# RGBW_Controller31.net
KiCad netlist of a schematic drawn in EAGLE
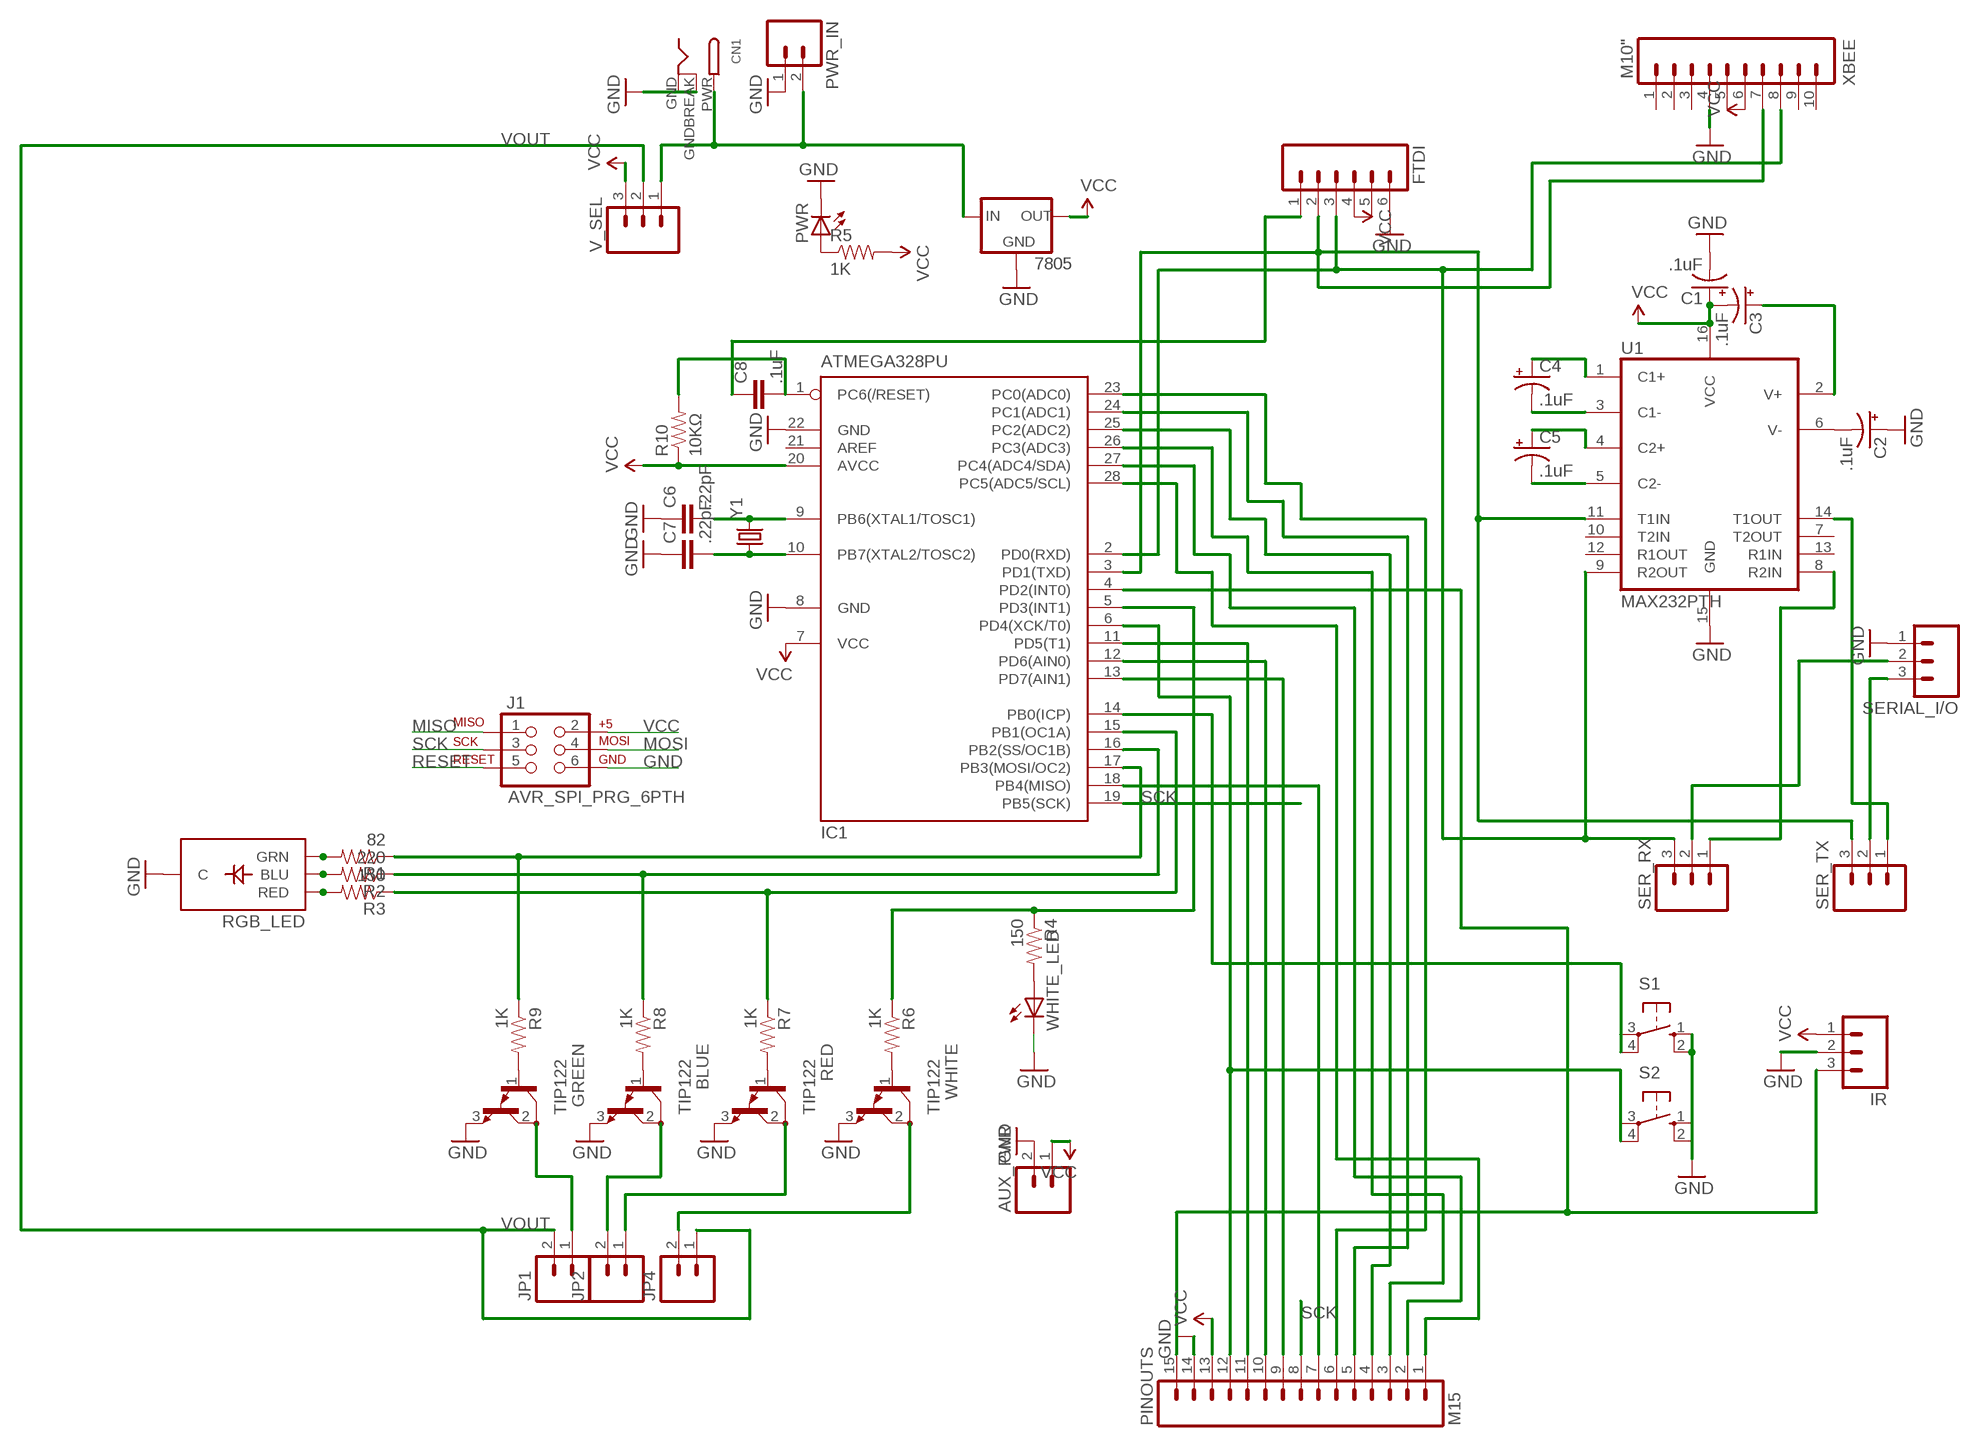
[diagram p0: schematic, sheet 1]

(export (version "E")
  (design (tool "Eeschema 10.0.6"))
  (components
    (comp (ref "7805")
      (value "V_REG_78XXSIDE")
      (footprint "eagle-import:78XXL")
      (libsource (lib "eagle-import") (part "V_REG_78XXSIDE"))
    )
    (comp (ref "AUX_PWR")
      (value "M02PTH")
      (footprint "eagle-import:1X02")
      (libsource (lib "eagle-import") (part "M02PTH"))
    )
    (comp (ref "BLUE")
      (value "TIP122")
      (footprint "eagle-import:TO220")
      (libsource (lib "eagle-import") (part "TIP122"))
    )
    (comp (ref "C1")
      (value ".1uF")
      (footprint "eagle-import:CPOL-RADIAL-100UF-25V")
      (libsource (lib "eagle-import") (part "CAP_POLPTH1"))
    )
    (comp (ref "C2")
      (value ".1uF")
      (footprint "eagle-import:CPOL-RADIAL-100UF-25V")
      (libsource (lib "eagle-import") (part "CAP_POLPTH1"))
    )
    (comp (ref "C3")
      (value ".1uF")
      (footprint "eagle-import:CPOL-RADIAL-100UF-25V")
      (libsource (lib "eagle-import") (part "CAP_POLPTH1"))
    )
    (comp (ref "C4")
      (value ".1uF")
      (footprint "eagle-import:CPOL-RADIAL-100UF-25V")
      (libsource (lib "eagle-import") (part "CAP_POLPTH1"))
    )
    (comp (ref "C5")
      (value ".1uF")
      (footprint "eagle-import:CPOL-RADIAL-100UF-25V")
      (libsource (lib "eagle-import") (part "CAP_POLPTH1"))
    )
    (comp (ref "C6")
      (value ".22pF")
      (footprint "eagle-import:CAP-PTH-SMALL")
      (libsource (lib "eagle-import") (part "CAPPTH"))
    )
    (comp (ref "C7")
      (value ".22pF")
      (footprint "eagle-import:CAP-PTH-SMALL")
      (libsource (lib "eagle-import") (part "CAPPTH"))
    )
    (comp (ref "C8")
      (value ".1uF")
      (footprint "eagle-import:CAP-PTH-SMALL-KIT")
      (libsource (lib "eagle-import") (part "CAPKIT"))
    )
    (comp (ref "CN1")
      (value "DCBARRELPTH")
      (footprint "eagle-import:DCJACK_2MM_PTH")
      (libsource (lib "eagle-import") (part "DCBARRELPTH"))
    )
    (comp (ref "FTDI")
      (value "M06SIP")
      (footprint "eagle-import:1X06")
      (libsource (lib "eagle-import") (part "M06SIP"))
    )
    (comp (ref "GREEN")
      (value "TIP122")
      (footprint "eagle-import:TO220")
      (libsource (lib "eagle-import") (part "TIP122"))
    )
    (comp (ref "IC1")
      (value "ATMEGA328PU")
      (footprint "eagle-import:DIL28-3")
      (libsource (lib "eagle-import") (part "MEGA8-P"))
    )
    (comp (ref "IR")
      (value "M03PTH")
      (footprint "eagle-import:1X03")
      (libsource (lib "eagle-import") (part "M03PTH"))
    )
    (comp (ref "J1")
      (value "AVR_SPI_PRG_6PTH")
      (footprint "eagle-import:2X3")
      (libsource (lib "eagle-import") (part "AVR_SPI_PRG_6PTH"))
    )
    (comp (ref "JP1")
      (value "M025MM")
      (footprint "eagle-import:SCREWTERMINAL-5MM-2")
      (libsource (lib "eagle-import") (part "M025MM"))
    )
    (comp (ref "JP2")
      (value "M025MM")
      (footprint "eagle-import:SCREWTERMINAL-5MM-2")
      (libsource (lib "eagle-import") (part "M025MM"))
    )
    (comp (ref "JP4")
      (value "M025MM")
      (footprint "eagle-import:SCREWTERMINAL-5MM-2")
      (libsource (lib "eagle-import") (part "M025MM"))
    )
    (comp (ref "PINOUTS")
      (value "M15")
      (footprint "eagle-import:1X15")
      (libsource (lib "eagle-import") (part "M15"))
    )
    (comp (ref "PWR")
      (value "LED5MM")
      (footprint "eagle-import:LED5MM")
      (libsource (lib "eagle-import") (part "LED5MM"))
    )
    (comp (ref "PWR_IN")
      (value "M025MM")
      (footprint "eagle-import:SCREWTERMINAL-5MM-2")
      (libsource (lib "eagle-import") (part "M025MM"))
    )
    (comp (ref "R1")
      (value "82")
      (footprint "eagle-import:AXIAL-0.4")
      (libsource (lib "eagle-import") (part "RESISTORPTH-1/4W"))
    )
    (comp (ref "R2")
      (value "220")
      (footprint "eagle-import:AXIAL-0.4")
      (libsource (lib "eagle-import") (part "RESISTORPTH-1/4W"))
    )
    (comp (ref "R3")
      (value "150")
      (footprint "eagle-import:AXIAL-0.4")
      (libsource (lib "eagle-import") (part "RESISTORPTH-1/4W"))
    )
    (comp (ref "R4")
      (value "150")
      (footprint "eagle-import:AXIAL-0.4")
      (libsource (lib "eagle-import") (part "RESISTORPTH-1/4W"))
    )
    (comp (ref "R5")
      (value "1K")
      (footprint "eagle-import:AXIAL-0.4")
      (libsource (lib "eagle-import") (part "RESISTORPTH-1/4W"))
    )
    (comp (ref "R6")
      (value "1K")
      (footprint "eagle-import:AXIAL-0.4")
      (libsource (lib "eagle-import") (part "RESISTORPTH-1/4W"))
    )
    (comp (ref "R7")
      (value "1K")
      (footprint "eagle-import:AXIAL-0.4")
      (libsource (lib "eagle-import") (part "RESISTORPTH-1/4W"))
    )
    (comp (ref "R8")
      (value "1K")
      (footprint "eagle-import:AXIAL-0.4")
      (libsource (lib "eagle-import") (part "RESISTORPTH-1/4W"))
    )
    (comp (ref "R9")
      (value "1K")
      (footprint "eagle-import:AXIAL-0.4")
      (libsource (lib "eagle-import") (part "RESISTORPTH-1/4W"))
    )
    (comp (ref "R10")
      (value "10KΩ")
      (footprint "eagle-import:AXIAL-0.4")
      (libsource (lib "eagle-import") (part "RESISTORPTH-1/4W"))
    )
    (comp (ref "RED")
      (value "TIP122")
      (footprint "eagle-import:TO220")
      (libsource (lib "eagle-import") (part "TIP122"))
    )
    (comp (ref "RGB_LED")
      (value "LED-TRICOLOR-THROUGHHOLE")
      (footprint "eagle-import:LED-TRICOLOR-THROUGHHOLE")
      (libsource (lib "eagle-import") (part "LED-TRICOLOR-THROUGHHOLE"))
    )
    (comp (ref "S1")
      (value "10-XX")
      (footprint "eagle-import:B3F-10XX")
      (fields (field (name "MPN") "B3F-1000"))
      (libsource (lib "eagle-import") (part "10-XX"))
    )
    (comp (ref "S2")
      (value "10-XX")
      (footprint "eagle-import:B3F-10XX")
      (fields (field (name "MPN") "B3F-1000"))
      (libsource (lib "eagle-import") (part "10-XX"))
    )
    (comp (ref "SERIAL_I/O")
      (value "M03SCREW")
      (footprint "eagle-import:SCREWTERMINAL-3.5MM-3")
      (libsource (lib "eagle-import") (part "M03SCREW"))
    )
    (comp (ref "SER_RX")
      (value "M03PTH")
      (footprint "eagle-import:1X03")
      (libsource (lib "eagle-import") (part "M03PTH"))
    )
    (comp (ref "SER_TX")
      (value "M03PTH")
      (footprint "eagle-import:1X03")
      (libsource (lib "eagle-import") (part "M03PTH"))
    )
    (comp (ref "U1")
      (value "MAX232PTH")
      (footprint "eagle-import:DIL16")
      (libsource (lib "eagle-import") (part "MAX232PTH"))
    )
    (comp (ref "V_SEL")
      (value "M03PTH")
      (footprint "eagle-import:1X03")
      (libsource (lib "eagle-import") (part "M03PTH"))
    )
    (comp (ref "WHITE")
      (value "TIP122")
      (footprint "eagle-import:TO220")
      (libsource (lib "eagle-import") (part "TIP122"))
    )
    (comp (ref "WHITE_LED")
      (value "LED5MM")
      (footprint "eagle-import:LED5MM")
      (libsource (lib "eagle-import") (part "LED5MM"))
    )
    (comp (ref "XBEE")
      (value "M10\"")
      (footprint "eagle-import:1X10")
      (libsource (lib "eagle-import") (part "M10{dblquote}"))
    )
    (comp (ref "Y1")
      (value "CRYSTALHC49US")
      (footprint "eagle-import:HC49US")
      (libsource (lib "eagle-import") (part "CRYSTALHC49US"))
    )
  )
  (nets
    (net (code "1") (name "/MISO") (class "Default")
      (node (ref "IC1") (pin "18") (pinfunction "PB4(MISO)_18") (pintype "bidirectional"))
      (node (ref "J1") (pin "1") (pinfunction "1_1") (pintype "passive"))
      (node (ref "PINOUTS") (pin "7") (pinfunction "7_7") (pintype "passive"))
    )
    (net (code "2") (name "/MOSI") (class "Default")
      (node (ref "IC1") (pin "17") (pinfunction "PB3(MOSI/OC2)_17") (pintype "bidirectional"))
      (node (ref "J1") (pin "4") (pinfunction "4_4") (pintype "passive"))
      (node (ref "R1") (pin "P$1") (pinfunction "1_P$1") (pintype "passive"))
      (node (ref "R9") (pin "P$1") (pinfunction "1_P$1") (pintype "passive"))
    )
    (net (code "3") (name "/RESET") (class "Default")
      (node (ref "C8") (pin "2") (pinfunction "2_2") (pintype "passive"))
      (node (ref "IC1") (pin "1") (pinfunction "PC6(/RESET)_1") (pintype "bidirectional"))
      (node (ref "J1") (pin "5") (pinfunction "5_5") (pintype "passive"))
      (node (ref "R10") (pin "P$2") (pinfunction "2_P$2") (pintype "passive"))
    )
    (net (code "4") (name "/SCK") (class "Default")
      (node (ref "IC1") (pin "19") (pinfunction "PB5(SCK)_19") (pintype "bidirectional"))
      (node (ref "J1") (pin "3") (pinfunction "3_3") (pintype "passive"))
      (node (ref "PINOUTS") (pin "8") (pinfunction "8_8") (pintype "passive"))
    )
    (net (code "5") (name "/VOUT") (class "Default")
      (node (ref "JP1") (pin "2") (pinfunction "2_2") (pintype "passive"))
      (node (ref "JP4") (pin "1") (pinfunction "1_1") (pintype "passive"))
      (node (ref "V_SEL") (pin "2") (pinfunction "2_2") (pintype "passive"))
    )
    (net (code "6") (name "GND") (class "Default")
      (node (ref "7805") (pin "GND") (pinfunction "GND_GND") (pintype "input"))
      (node (ref "AUX_PWR") (pin "2") (pinfunction "2_2") (pintype "passive"))
      (node (ref "BLUE") (pin "3") (pinfunction "E_3") (pintype "passive"))
      (node (ref "C1") (pin "2") (pinfunction "-_2") (pintype "passive"))
      (node (ref "C2") (pin "1") (pinfunction "+_1") (pintype "passive"))
      (node (ref "C6") (pin "1") (pinfunction "1_1") (pintype "passive"))
      (node (ref "C7") (pin "1") (pinfunction "1_1") (pintype "passive"))
      (node (ref "CN1") (pin "GND") (pinfunction "GND_GND") (pintype "power_in"))
      (node (ref "CN1") (pin "GNDBREAK") (pinfunction "GNDBREAK_GNDBREAK") (pintype "power_in"))
      (node (ref "FTDI") (pin "6") (pinfunction "6_6") (pintype "passive"))
      (node (ref "GREEN") (pin "3") (pinfunction "E_3") (pintype "passive"))
      (node (ref "IC1") (pin "22") (pinfunction "GND_22") (pintype "power_in"))
      (node (ref "IC1") (pin "8") (pinfunction "GND_8") (pintype "power_in"))
      (node (ref "IR") (pin "2") (pinfunction "2_2") (pintype "passive"))
      (node (ref "J1") (pin "6") (pinfunction "6_6") (pintype "passive"))
      (node (ref "PINOUTS") (pin "14") (pinfunction "14_14") (pintype "passive"))
      (node (ref "PWR") (pin "K") (pinfunction "C_K") (pintype "passive"))
      (node (ref "PWR_IN") (pin "1") (pinfunction "1_1") (pintype "passive"))
      (node (ref "RED") (pin "3") (pinfunction "E_3") (pintype "passive"))
      (node (ref "RGB_LED") (pin "GND") (pinfunction "C_GND") (pintype "bidirectional"))
      (node (ref "S1") (pin "1") (pinfunction "S_1") (pintype "passive"))
      (node (ref "S1") (pin "2") (pinfunction "S1_2") (pintype "passive"))
      (node (ref "S2") (pin "1") (pinfunction "S_1") (pintype "passive"))
      (node (ref "S2") (pin "2") (pinfunction "S1_2") (pintype "passive"))
      (node (ref "SERIAL_I/O") (pin "1") (pinfunction "1_1") (pintype "passive"))
      (node (ref "U1") (pin "15") (pinfunction "GND_15") (pintype "bidirectional"))
      (node (ref "WHITE") (pin "3") (pinfunction "E_3") (pintype "passive"))
      (node (ref "WHITE_LED") (pin "K") (pinfunction "C_K") (pintype "passive"))
      (node (ref "XBEE") (pin "4") (pinfunction "4_4") (pintype "passive"))
    )
    (net (code "7") (name "Net-(7805-PadIN)") (class "Default")
      (node (ref "7805") (pin "IN") (pinfunction "IN_IN") (pintype "input"))
      (node (ref "CN1") (pin "PWR") (pinfunction "PWR_PWR") (pintype "power_in"))
      (node (ref "PWR_IN") (pin "2") (pinfunction "2_2") (pintype "passive"))
      (node (ref "V_SEL") (pin "1") (pinfunction "1_1") (pintype "passive"))
    )
    (net (code "8") (name "Net-(BLUE-B)") (class "Default")
      (node (ref "BLUE") (pin "1") (pinfunction "B_1") (pintype "passive"))
      (node (ref "R8") (pin "P$2") (pinfunction "2_P$2") (pintype "passive"))
    )
    (net (code "9") (name "Net-(BLUE-C)") (class "Default")
      (node (ref "BLUE") (pin "2") (pinfunction "C_2") (pintype "passive"))
      (node (ref "JP2") (pin "2") (pinfunction "2_2") (pintype "passive"))
    )
    (net (code "10") (name "Net-(C2--)") (class "Default")
      (node (ref "C2") (pin "2") (pinfunction "-_2") (pintype "passive"))
      (node (ref "U1") (pin "6") (pinfunction "V-_6") (pintype "bidirectional"))
    )
    (net (code "11") (name "Net-(C3-+)") (class "Default")
      (node (ref "C3") (pin "1") (pinfunction "+_1") (pintype "passive"))
      (node (ref "U1") (pin "2") (pinfunction "V+_2") (pintype "bidirectional"))
    )
    (net (code "12") (name "Net-(C4-+)") (class "Default")
      (node (ref "C4") (pin "1") (pinfunction "+_1") (pintype "passive"))
      (node (ref "U1") (pin "1") (pinfunction "C1+_1") (pintype "bidirectional"))
    )
    (net (code "13") (name "Net-(C4--)") (class "Default")
      (node (ref "C4") (pin "2") (pinfunction "-_2") (pintype "passive"))
      (node (ref "U1") (pin "3") (pinfunction "C1-_3") (pintype "bidirectional"))
    )
    (net (code "14") (name "Net-(C5-+)") (class "Default")
      (node (ref "C5") (pin "1") (pinfunction "+_1") (pintype "passive"))
      (node (ref "U1") (pin "4") (pinfunction "C2+_4") (pintype "bidirectional"))
    )
    (net (code "15") (name "Net-(C5--)") (class "Default")
      (node (ref "C5") (pin "2") (pinfunction "-_2") (pintype "passive"))
      (node (ref "U1") (pin "5") (pinfunction "C2-_5") (pintype "bidirectional"))
    )
    (net (code "16") (name "Net-(C8-Pad1)") (class "Default")
      (node (ref "C8") (pin "1") (pinfunction "1_1") (pintype "passive"))
      (node (ref "FTDI") (pin "1") (pinfunction "1_1") (pintype "passive"))
    )
    (net (code "17") (name "Net-(GREEN-B)") (class "Default")
      (node (ref "GREEN") (pin "1") (pinfunction "B_1") (pintype "passive"))
      (node (ref "R9") (pin "P$2") (pinfunction "2_P$2") (pintype "passive"))
    )
    (net (code "18") (name "Net-(GREEN-C)") (class "Default")
      (node (ref "GREEN") (pin "2") (pinfunction "C_2") (pintype "passive"))
      (node (ref "JP1") (pin "1") (pinfunction "1_1") (pintype "passive"))
    )
    (net (code "19") (name "Net-(IC1-PB0(ICP))") (class "Default")
      (node (ref "IC1") (pin "14") (pinfunction "PB0(ICP)_14") (pintype "bidirectional"))
      (node (ref "S1") (pin "3") (pinfunction "P_3") (pintype "passive"))
      (node (ref "S1") (pin "4") (pinfunction "P1_4") (pintype "passive"))
    )
    (net (code "20") (name "Net-(IC1-PB1(OC1A))") (class "Default")
      (node (ref "IC1") (pin "15") (pinfunction "PB1(OC1A)_15") (pintype "bidirectional"))
      (node (ref "R3") (pin "P$1") (pinfunction "1_P$1") (pintype "passive"))
      (node (ref "R7") (pin "P$1") (pinfunction "1_P$1") (pintype "passive"))
    )
    (net (code "21") (name "Net-(IC1-PB2(SS{slash}OC1B))") (class "Default")
      (node (ref "IC1") (pin "16") (pinfunction "PB2(SS/OC1B)_16") (pintype "bidirectional"))
      (node (ref "R2") (pin "P$1") (pinfunction "1_P$1") (pintype "passive"))
      (node (ref "R8") (pin "P$1") (pinfunction "1_P$1") (pintype "passive"))
    )
    (net (code "22") (name "Net-(IC1-PB6(XTAL1{slash}TOSC1))") (class "Default")
      (node (ref "C6") (pin "2") (pinfunction "2_2") (pintype "passive"))
      (node (ref "IC1") (pin "9") (pinfunction "PB6(XTAL1/TOSC1)_9") (pintype "bidirectional"))
      (node (ref "Y1") (pin "2") (pinfunction "2_2") (pintype "passive"))
    )
    (net (code "23") (name "Net-(IC1-PB7(XTAL2{slash}TOSC2))") (class "Default")
      (node (ref "C7") (pin "2") (pinfunction "2_2") (pintype "passive"))
      (node (ref "IC1") (pin "10") (pinfunction "PB7(XTAL2/TOSC2)_10") (pintype "bidirectional"))
      (node (ref "Y1") (pin "1") (pinfunction "1_1") (pintype "passive"))
    )
    (net (code "24") (name "Net-(IC1-PC0(ADC0))") (class "Default")
      (node (ref "IC1") (pin "23") (pinfunction "PC0(ADC0)_23") (pintype "bidirectional"))
      (node (ref "PINOUTS") (pin "6") (pinfunction "6_6") (pintype "passive"))
    )
    (net (code "25") (name "Net-(IC1-PC1(ADC1))") (class "Default")
      (node (ref "IC1") (pin "24") (pinfunction "PC1(ADC1)_24") (pintype "bidirectional"))
      (node (ref "PINOUTS") (pin "5") (pinfunction "5_5") (pintype "passive"))
    )
    (net (code "26") (name "Net-(IC1-PC2(ADC2))") (class "Default")
      (node (ref "IC1") (pin "25") (pinfunction "PC2(ADC2)_25") (pintype "bidirectional"))
      (node (ref "PINOUTS") (pin "4") (pinfunction "4_4") (pintype "passive"))
    )
    (net (code "27") (name "Net-(IC1-PC3(ADC3))") (class "Default")
      (node (ref "IC1") (pin "26") (pinfunction "PC3(ADC3)_26") (pintype "bidirectional"))
      (node (ref "PINOUTS") (pin "3") (pinfunction "3_3") (pintype "passive"))
    )
    (net (code "28") (name "Net-(IC1-PC4(ADC4{slash}SDA))") (class "Default")
      (node (ref "IC1") (pin "27") (pinfunction "PC4(ADC4/SDA)_27") (pintype "bidirectional"))
      (node (ref "PINOUTS") (pin "2") (pinfunction "2_2") (pintype "passive"))
    )
    (net (code "29") (name "Net-(IC1-PC5(ADC5{slash}SCL))") (class "Default")
      (node (ref "IC1") (pin "28") (pinfunction "PC5(ADC5/SCL)_28") (pintype "bidirectional"))
      (node (ref "PINOUTS") (pin "1") (pinfunction "1_1") (pintype "passive"))
    )
    (net (code "30") (name "Net-(IC1-PD0(RXD))") (class "Default")
      (node (ref "FTDI") (pin "3") (pinfunction "3_3") (pintype "passive"))
      (node (ref "IC1") (pin "2") (pinfunction "PD0(RXD)_2") (pintype "bidirectional"))
      (node (ref "SER_RX") (pin "3") (pinfunction "3_3") (pintype "passive"))
      (node (ref "U1") (pin "9") (pinfunction "R2OUT_9") (pintype "output"))
      (node (ref "XBEE") (pin "8") (pinfunction "8_8") (pintype "passive"))
    )
    (net (code "31") (name "Net-(IC1-PD1(TXD))") (class "Default")
      (node (ref "FTDI") (pin "2") (pinfunction "2_2") (pintype "passive"))
      (node (ref "IC1") (pin "3") (pinfunction "PD1(TXD)_3") (pintype "bidirectional"))
      (node (ref "SER_TX") (pin "3") (pinfunction "3_3") (pintype "passive"))
      (node (ref "U1") (pin "11") (pinfunction "T1IN_11") (pintype "input"))
      (node (ref "XBEE") (pin "7") (pinfunction "7_7") (pintype "passive"))
    )
    (net (code "32") (name "Net-(IC1-PD2(INT0))") (class "Default")
      (node (ref "IC1") (pin "4") (pinfunction "PD2(INT0)_4") (pintype "bidirectional"))
      (node (ref "IR") (pin "3") (pinfunction "3_3") (pintype "passive"))
      (node (ref "PINOUTS") (pin "15") (pinfunction "15_15") (pintype "passive"))
    )
    (net (code "33") (name "Net-(IC1-PD3(INT1))") (class "Default")
      (node (ref "IC1") (pin "5") (pinfunction "PD3(INT1)_5") (pintype "bidirectional"))
      (node (ref "R4") (pin "P$1") (pinfunction "1_P$1") (pintype "passive"))
      (node (ref "R6") (pin "P$1") (pinfunction "1_P$1") (pintype "passive"))
    )
    (net (code "34") (name "Net-(IC1-PD4(XCK{slash}T0))") (class "Default")
      (node (ref "IC1") (pin "6") (pinfunction "PD4(XCK/T0)_6") (pintype "bidirectional"))
      (node (ref "PINOUTS") (pin "12") (pinfunction "12_12") (pintype "passive"))
      (node (ref "S2") (pin "3") (pinfunction "P_3") (pintype "passive"))
      (node (ref "S2") (pin "4") (pinfunction "P1_4") (pintype "passive"))
    )
    (net (code "35") (name "Net-(IC1-PD5(T1))") (class "Default")
      (node (ref "IC1") (pin "11") (pinfunction "PD5(T1)_11") (pintype "bidirectional"))
      (node (ref "PINOUTS") (pin "11") (pinfunction "11_11") (pintype "passive"))
    )
    (net (code "36") (name "Net-(IC1-PD6(AIN0))") (class "Default")
      (node (ref "IC1") (pin "12") (pinfunction "PD6(AIN0)_12") (pintype "bidirectional"))
      (node (ref "PINOUTS") (pin "10") (pinfunction "10_10") (pintype "passive"))
    )
    (net (code "37") (name "Net-(IC1-PD7(AIN1))") (class "Default")
      (node (ref "IC1") (pin "13") (pinfunction "PD7(AIN1)_13") (pintype "bidirectional"))
      (node (ref "PINOUTS") (pin "9") (pinfunction "9_9") (pintype "passive"))
    )
    (net (code "38") (name "Net-(R1-2)") (class "Default")
      (node (ref "R1") (pin "P$2") (pinfunction "2_P$2") (pintype "passive"))
      (node (ref "RGB_LED") (pin "GRN") (pinfunction "GRN_GRN") (pintype "bidirectional"))
    )
    (net (code "39") (name "Net-(R2-2)") (class "Default")
      (node (ref "R2") (pin "P$2") (pinfunction "2_P$2") (pintype "passive"))
      (node (ref "RGB_LED") (pin "BLU") (pinfunction "BLU_BLU") (pintype "bidirectional"))
    )
    (net (code "40") (name "Net-(R3-2)") (class "Default")
      (node (ref "R3") (pin "P$2") (pinfunction "2_P$2") (pintype "passive"))
      (node (ref "RGB_LED") (pin "RED") (pinfunction "RED_RED") (pintype "bidirectional"))
    )
    (net (code "41") (name "Net-(R4-2)") (class "Default")
      (node (ref "R4") (pin "P$2") (pinfunction "2_P$2") (pintype "passive"))
      (node (ref "WHITE_LED") (pin "A") (pinfunction "A_A") (pintype "passive"))
    )
    (net (code "42") (name "Net-(R5-1)") (class "Default")
      (node (ref "PWR") (pin "A") (pinfunction "A_A") (pintype "passive"))
      (node (ref "R5") (pin "P$1") (pinfunction "1_P$1") (pintype "passive"))
    )
    (net (code "43") (name "Net-(R6-2)") (class "Default")
      (node (ref "R6") (pin "P$2") (pinfunction "2_P$2") (pintype "passive"))
      (node (ref "WHITE") (pin "1") (pinfunction "B_1") (pintype "passive"))
    )
    (net (code "44") (name "Net-(R7-2)") (class "Default")
      (node (ref "R7") (pin "P$2") (pinfunction "2_P$2") (pintype "passive"))
      (node (ref "RED") (pin "1") (pinfunction "B_1") (pintype "passive"))
    )
    (net (code "45") (name "Net-(RED-C)") (class "Default")
      (node (ref "JP2") (pin "1") (pinfunction "1_1") (pintype "passive"))
      (node (ref "RED") (pin "2") (pinfunction "C_2") (pintype "passive"))
    )
    (net (code "46") (name "Net-(SERIAL_I/O-Pad2)") (class "Default")
      (node (ref "SERIAL_I/O") (pin "2") (pinfunction "2_2") (pintype "passive"))
      (node (ref "SER_RX") (pin "2") (pinfunction "2_2") (pintype "passive"))
    )
    (net (code "47") (name "Net-(SERIAL_I/O-Pad3)") (class "Default")
      (node (ref "SERIAL_I/O") (pin "3") (pinfunction "3_3") (pintype "passive"))
      (node (ref "SER_TX") (pin "2") (pinfunction "2_2") (pintype "passive"))
    )
    (net (code "48") (name "Net-(U1-R2IN)") (class "Default")
      (node (ref "SER_RX") (pin "1") (pinfunction "1_1") (pintype "passive"))
      (node (ref "U1") (pin "8") (pinfunction "R2IN_8") (pintype "input"))
    )
    (net (code "49") (name "Net-(U1-T1OUT)") (class "Default")
      (node (ref "SER_TX") (pin "1") (pinfunction "1_1") (pintype "passive"))
      (node (ref "U1") (pin "14") (pinfunction "T1OUT_14") (pintype "output"))
    )
    (net (code "50") (name "Net-(WHITE-C)") (class "Default")
      (node (ref "JP4") (pin "2") (pinfunction "2_2") (pintype "passive"))
      (node (ref "WHITE") (pin "2") (pinfunction "C_2") (pintype "passive"))
    )
    (net (code "51") (name "VCC") (class "Default")
      (node (ref "7805") (pin "OUT") (pinfunction "OUT_OUT") (pintype "output"))
      (node (ref "AUX_PWR") (pin "1") (pinfunction "1_1") (pintype "passive"))
      (node (ref "C1") (pin "1") (pinfunction "+_1") (pintype "passive"))
      (node (ref "C3") (pin "2") (pinfunction "-_2") (pintype "passive"))
      (node (ref "FTDI") (pin "4") (pinfunction "4_4") (pintype "passive"))
      (node (ref "IC1") (pin "20") (pinfunction "AVCC_20") (pintype "power_in"))
      (node (ref "IC1") (pin "7") (pinfunction "VCC_7") (pintype "power_in"))
      (node (ref "IR") (pin "1") (pinfunction "1_1") (pintype "passive"))
      (node (ref "J1") (pin "2") (pinfunction "2_2") (pintype "passive"))
      (node (ref "PINOUTS") (pin "13") (pinfunction "13_13") (pintype "passive"))
      (node (ref "R10") (pin "P$1") (pinfunction "1_P$1") (pintype "passive"))
      (node (ref "R5") (pin "P$2") (pinfunction "2_P$2") (pintype "passive"))
      (node (ref "U1") (pin "16") (pinfunction "VCC_16") (pintype "bidirectional"))
      (node (ref "V_SEL") (pin "3") (pinfunction "3_3") (pintype "passive"))
      (node (ref "XBEE") (pin "6") (pinfunction "6_6") (pintype "passive"))
    )
    (net (code "52") (name "unconnected-(FTDI-Pad5)") (class "Default")
      (node (ref "FTDI") (pin "5") (pinfunction "5_5") (pintype "passive"))
    )
    (net (code "53") (name "unconnected-(IC1-AREF-Pad21)") (class "Default")
      (node (ref "IC1") (pin "21") (pinfunction "AREF_21") (pintype "passive"))
    )
    (net (code "54") (name "unconnected-(U1-R1IN-Pad13)") (class "Default")
      (node (ref "U1") (pin "13") (pinfunction "R1IN_13") (pintype "input"))
    )
    (net (code "55") (name "unconnected-(U1-R1OUT-Pad12)") (class "Default")
      (node (ref "U1") (pin "12") (pinfunction "R1OUT_12") (pintype "output"))
    )
    (net (code "56") (name "unconnected-(U1-T2IN-Pad10)") (class "Default")
      (node (ref "U1") (pin "10") (pinfunction "T2IN_10") (pintype "input"))
    )
    (net (code "57") (name "unconnected-(U1-T2OUT-Pad7)") (class "Default")
      (node (ref "U1") (pin "7") (pinfunction "T2OUT_7") (pintype "output"))
    )
    (net (code "58") (name "unconnected-(XBEE-Pad1)") (class "Default")
      (node (ref "XBEE") (pin "1") (pinfunction "1_1") (pintype "passive"))
    )
    (net (code "59") (name "unconnected-(XBEE-Pad2)") (class "Default")
      (node (ref "XBEE") (pin "2") (pinfunction "2_2") (pintype "passive"))
    )
    (net (code "60") (name "unconnected-(XBEE-Pad3)") (class "Default")
      (node (ref "XBEE") (pin "3") (pinfunction "3_3") (pintype "passive"))
    )
    (net (code "61") (name "unconnected-(XBEE-Pad5)") (class "Default")
      (node (ref "XBEE") (pin "5") (pinfunction "5_5") (pintype "passive"))
    )
    (net (code "62") (name "unconnected-(XBEE-Pad9)") (class "Default")
      (node (ref "XBEE") (pin "9") (pinfunction "9_9") (pintype "passive"))
    )
    (net (code "63") (name "unconnected-(XBEE-Pad10)") (class "Default")
      (node (ref "XBEE") (pin "10") (pinfunction "10_10") (pintype "passive"))
    )
  )
)
